# catropy.net
KiCad netlist of a schematic drawn in EAGLE
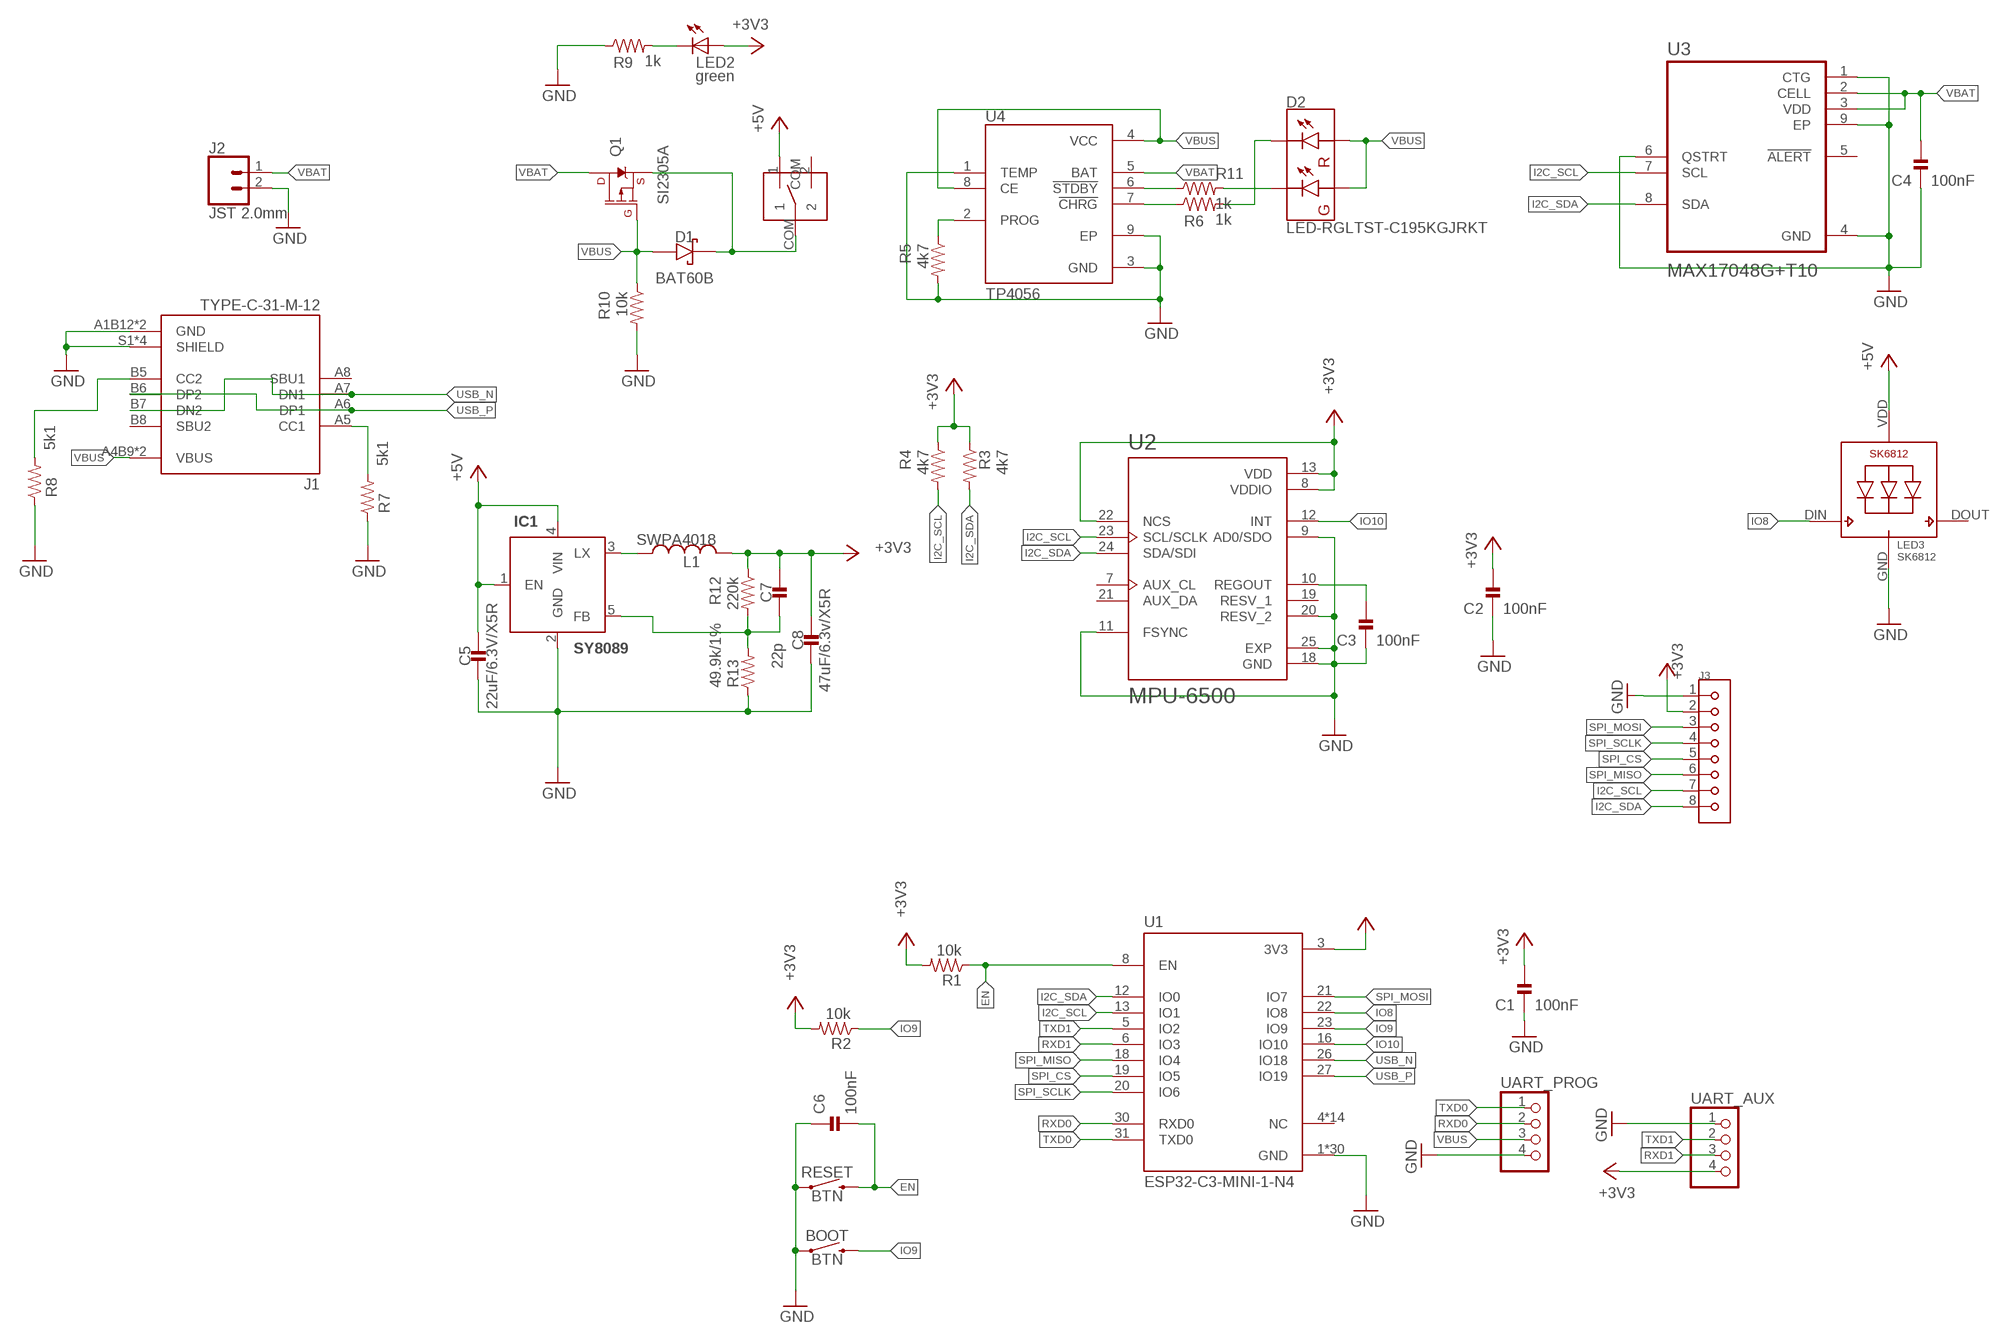
[diagram p0: schematic, sheet 1]

(export (version "E")
  (design (tool "Eeschema 10.0.6"))
  (components
    (comp (ref "BOOT")
      (value "BTN")
      (footprint "eagle-import:TACTILE_SWITCH_SMD_6.0X3.5MM")
      (fields (field (name "LCSC_PART") "C118141"))
      (libsource (lib "eagle-import") (part "MOMENTARY-SWITCH-SPST-SMD-6.0X3.5MM"))
    )
    (comp (ref "C1")
      (value "100nF")
      (footprint "eagle-import:0402_CAP")
      (libsource (lib "eagle-import") (part "CAPACITOR0402_CAP"))
    )
    (comp (ref "C2")
      (value "100nF")
      (footprint "eagle-import:0402_CAP")
      (libsource (lib "eagle-import") (part "CAPACITOR0402_CAP"))
    )
    (comp (ref "C3")
      (value "100nF")
      (footprint "eagle-import:0402_CAP")
      (libsource (lib "eagle-import") (part "CAPACITOR0402_CAP"))
    )
    (comp (ref "C4")
      (value "100nF")
      (footprint "eagle-import:0402_CAP")
      (libsource (lib "eagle-import") (part "CAPACITOR0402_CAP"))
    )
    (comp (ref "C5")
      (value "22uF/6.3V/X5R")
      (footprint "eagle-import:0603_CAP")
      (libsource (lib "eagle-import") (part "CAPACITOR0603_CAP"))
    )
    (comp (ref "C6")
      (value "100nF")
      (footprint "eagle-import:0402_CAP")
      (libsource (lib "eagle-import") (part "CAPACITOR0402_CAP"))
    )
    (comp (ref "C7")
      (value "22p")
      (footprint "eagle-import:0402_CAP")
      (libsource (lib "eagle-import") (part "CAPACITOR0402_CAP"))
    )
    (comp (ref "C8")
      (value "47uF/6.3v/X5R")
      (footprint "eagle-import:0805_CAP")
      (libsource (lib "eagle-import") (part "CAPACITOR0805_CAP"))
    )
    (comp (ref "D1")
      (value "BAT60B")
      (footprint "eagle-import:SOD323")
      (fields (field (name "LCSC_PART") "C22638"))
      (libsource (lib "eagle-import") (part "DIODE_SCHOTTKYSOD323"))
    )
    (comp (ref "D2")
      (value "LED-RGLTST-C195KGJRKT")
      (footprint "eagle-import:LTST-C195KGJRKT")
      (fields (field (name "LCSC_PART") "C125104"))
      (libsource (lib "eagle-import") (part "LED-RGLTST-C195KGJRKT"))
    )
    (comp (ref "IC1")
      (value "SY8089")
      (footprint "eagle-import:SOT23-5")
      (fields (field (name "LCSC_PART") "C78988"))
      (libsource (lib "eagle-import") (part "SY8089"))
    )
    (comp (ref "J1")
      (value "TYPE-C-31-M-12")
      (footprint "eagle-import:HRO_TYPE-C-31-M-12")
      (fields (field (name "MF") "HRO Electronics Co., Ltd.") (field (name "LCSC_PART") "C165948"))
      (libsource (lib "eagle-import") (part "TYPE-C-31-M-12"))
    )
    (comp (ref "J2")
      (value "JST 2.0mm")
      (footprint "eagle-import:JST-2-SMD")
      (fields (field (name "LCSC_PART") "C3029440"))
      (libsource (lib "eagle-import") (part "CONN_02-JST-2MM-SMT"))
    )
    (comp (ref "J3")
      (value "SM08B-SRSS-TB(LF)(SN)")
      (footprint "eagle-import:JST_SM08B-SRSS-TB(LF)(SN)")
      (fields (field (name "MF") "JST Sales") (field (name "LCSC_PART") "C160407"))
      (libsource (lib "eagle-import") (part "SM08B-SRSS-TB(LF)(SN)"))
    )
    (comp (ref "L1")
      (value "SWPA4018")
      (footprint "eagle-import:SWPA40XX")
      (fields (field (name "LCSC_PART") "C50543"))
      (libsource (lib "eagle-import") (part "SWPA40XX"))
    )
    (comp (ref "LED2")
      (value "green")
      (footprint "eagle-import:CHIPLED_0603")
      (fields (field (name "LCSC_PART") "C72043"))
      (libsource (lib "eagle-import") (part "LEDCHIPLED_0603"))
    )
    (comp (ref "LED3")
      (value "SK6812")
      (footprint "eagle-import:LED_EC3210R")
      (fields (field (name "LCSC_PART") "C2890041"))
      (libsource (lib "eagle-import") (part "SK6812_EC3210R"))
    )
    (comp (ref "Q1")
      (value "SI2305A")
      (footprint "eagle-import:SOT23-3")
      (fields (field (name "LCSC_PART") "C347488"))
      (libsource (lib "eagle-import") (part "MOSFET_PCH-SI2309DS"))
    )
    (comp (ref "R1")
      (value "10k")
      (footprint "eagle-import:0402_RES")
      (libsource (lib "eagle-import") (part "RESISTOR0402_RES"))
    )
    (comp (ref "R2")
      (value "10k")
      (footprint "eagle-import:0402_RES")
      (libsource (lib "eagle-import") (part "RESISTOR0402_RES"))
    )
    (comp (ref "R3")
      (value "4k7")
      (footprint "eagle-import:0402_RES")
      (libsource (lib "eagle-import") (part "RESISTOR0402_RES"))
    )
    (comp (ref "R4")
      (value "4k7")
      (footprint "eagle-import:0402_RES")
      (libsource (lib "eagle-import") (part "RESISTOR0402_RES"))
    )
    (comp (ref "R5")
      (value "4k7")
      (footprint "eagle-import:0402_RES")
      (libsource (lib "eagle-import") (part "RESISTOR0402_RES"))
    )
    (comp (ref "R6")
      (value "1k")
      (footprint "eagle-import:0402_RES")
      (libsource (lib "eagle-import") (part "RESISTOR0402_RES"))
    )
    (comp (ref "R7")
      (value "5k1")
      (footprint "eagle-import:0402_RES")
      (libsource (lib "eagle-import") (part "RESISTOR0402_RES"))
    )
    (comp (ref "R8")
      (value "5k1")
      (footprint "eagle-import:0402_RES")
      (libsource (lib "eagle-import") (part "RESISTOR0402_RES"))
    )
    (comp (ref "R9")
      (value "1k")
      (footprint "eagle-import:0402_RES")
      (libsource (lib "eagle-import") (part "RESISTOR0402_RES"))
    )
    (comp (ref "R10")
      (value "10k")
      (footprint "eagle-import:0402_RES")
      (libsource (lib "eagle-import") (part "RESISTOR0402_RES"))
    )
    (comp (ref "R11")
      (value "1k")
      (footprint "eagle-import:0402_RES")
      (libsource (lib "eagle-import") (part "RESISTOR0402_RES"))
    )
    (comp (ref "R12")
      (value "220k")
      (footprint "eagle-import:0402_RES")
      (libsource (lib "eagle-import") (part "RESISTOR0402_RES"))
    )
    (comp (ref "R13")
      (value "49.9k/1%")
      (footprint "eagle-import:0402_RES")
      (fields (field (name "LCSC_PART") "C208898"))
      (libsource (lib "eagle-import") (part "RESISTOR0402_RES"))
    )
    (comp (ref "RESET")
      (value "BTN")
      (footprint "eagle-import:TACTILE_SWITCH_SMD_6.0X3.5MM")
      (fields (field (name "LCSC_PART") "C118141"))
      (libsource (lib "eagle-import") (part "MOMENTARY-SWITCH-SPST-SMD-6.0X3.5MM"))
    )
    (comp (ref "U$1")
      (value "SK12D07VG4")
      (footprint "eagle-import:SK12D07VG4")
      (fields (field (name "MF") "C&K") (field (name "LCSC_PART") "C393937"))
      (libsource (lib "eagle-import") (part "SK12D07VG4"))
    )
    (comp (ref "U1")
      (value "ESP32-C3-MINI-1-N4")
      (footprint "eagle-import:XCVR_ESP32-C3-MINI-1-N4")
      (fields (field (name "MF") "Espressif Systems") (field (name "LCSC_PART") "C2838502"))
      (libsource (lib "eagle-import") (part "ESP32-C3-MINI-1-N4"))
    )
    (comp (ref "U2")
      (value "MPU-6500")
      (footprint "eagle-import:QFN40P300X300X95-25N")
      (fields (field (name "MF") "TDK InvenSense") (field (name "LCSC_PART") "C50278"))
      (libsource (lib "eagle-import") (part "MPU-6500"))
    )
    (comp (ref "U3")
      (value "MAX17048G+T10")
      (footprint "eagle-import:SON50P200X200X80-9N")
      (fields (field (name "MF") "Analog Devices") (field (name "LCSC_PART") "C2682616"))
      (libsource (lib "eagle-import") (part "MAX17048G+T10"))
    )
    (comp (ref "U4")
      (value "TP4056")
      (footprint "eagle-import:SOP127P600X175-9N")
      (fields (field (name "MF") "NanJing Top Power ASIC Corp."))
      (libsource (lib "eagle-import") (part "TP4056"))
    )
    (comp (ref "UART_AUX")
      (value "PINHD-1X4")
      (footprint "eagle-import:1X04")
      (libsource (lib "eagle-import") (part "PINHD-1X4"))
    )
    (comp (ref "UART_PROG")
      (value "PINHD-1X4")
      (footprint "eagle-import:1X04")
      (libsource (lib "eagle-import") (part "PINHD-1X4"))
    )
  )
  (nets
    (net (code "1") (name "+3V3") (class "Default")
      (node (ref "C1") (pin "2") (pinfunction "2_2") (pintype "bidirectional"))
      (node (ref "C2") (pin "2") (pinfunction "2_2") (pintype "bidirectional"))
      (node (ref "C7") (pin "1") (pinfunction "1_1") (pintype "bidirectional"))
      (node (ref "C8") (pin "P$1") (pinfunction "1_P$1") (pintype "bidirectional"))
      (node (ref "J3") (pin "2") (pinfunction "2_2") (pintype "passive"))
      (node (ref "L1") (pin "P$2") (pinfunction "2_P$2") (pintype "bidirectional"))
      (node (ref "LED2") (pin "A") (pinfunction "A_A") (pintype "passive"))
      (node (ref "R1") (pin "2") (pinfunction "2_2") (pintype "passive"))
      (node (ref "R12") (pin "1") (pinfunction "1_1") (pintype "passive"))
      (node (ref "R2") (pin "2") (pinfunction "2_2") (pintype "passive"))
      (node (ref "R3") (pin "1") (pinfunction "1_1") (pintype "passive"))
      (node (ref "R4") (pin "1") (pinfunction "1_1") (pintype "passive"))
      (node (ref "U1") (pin "3") (pinfunction "3V3_3") (pintype "power_in"))
      (node (ref "U2") (pin "13") (pinfunction "VDD_13") (pintype "power_in"))
      (node (ref "U2") (pin "22") (pinfunction "NCS_22") (pintype "input"))
      (node (ref "U2") (pin "8") (pinfunction "VDDIO_8") (pintype "power_in"))
      (node (ref "UART_AUX") (pin "4") (pinfunction "4_4") (pintype "passive"))
    )
    (net (code "2") (name "+5V") (class "Default")
      (node (ref "C5") (pin "1") (pinfunction "1_1") (pintype "bidirectional"))
      (node (ref "IC1") (pin "1") (pinfunction "EN_1") (pintype "input"))
      (node (ref "IC1") (pin "4") (pinfunction "VIN_4") (pintype "input"))
      (node (ref "LED3") (pin "VDD") (pinfunction "VDD_VDD") (pintype "power_in"))
      (node (ref "U$1") (pin "1") (pinfunction "1_1") (pintype "bidirectional"))
    )
    (net (code "3") (name "EN") (class "Default")
      (node (ref "C6") (pin "2") (pinfunction "2_2") (pintype "bidirectional"))
      (node (ref "R1") (pin "1") (pinfunction "1_1") (pintype "passive"))
      (node (ref "RESET") (pin "2") (pinfunction "2_2") (pintype "passive"))
      (node (ref "U1") (pin "8") (pinfunction "EN_8") (pintype "input"))
    )
    (net (code "4") (name "GND") (class "Default")
      (node (ref "BOOT") (pin "1") (pinfunction "1_1") (pintype "passive"))
      (node (ref "C1") (pin "1") (pinfunction "1_1") (pintype "bidirectional"))
      (node (ref "C2") (pin "1") (pinfunction "1_1") (pintype "bidirectional"))
      (node (ref "C3") (pin "1") (pinfunction "1_1") (pintype "bidirectional"))
      (node (ref "C4") (pin "1") (pinfunction "1_1") (pintype "bidirectional"))
      (node (ref "C5") (pin "2") (pinfunction "2_2") (pintype "bidirectional"))
      (node (ref "C6") (pin "1") (pinfunction "1_1") (pintype "bidirectional"))
      (node (ref "C8") (pin "P$2") (pinfunction "2_P$2") (pintype "bidirectional"))
      (node (ref "IC1") (pin "2") (pinfunction "GND_2") (pintype "power_in"))
      (node (ref "J1") (pin "A1B12") (pinfunction "GND_A1B12") (pintype "power_in"))
      (node (ref "J1") (pin "B1A12") (pinfunction "GND_B1A12") (pintype "power_in"))
      (node (ref "J1") (pin "S1") (pinfunction "SHIELD_S1") (pintype "passive"))
      (node (ref "J1") (pin "S2") (pinfunction "SHIELD_S2") (pintype "passive"))
      (node (ref "J1") (pin "S3") (pinfunction "SHIELD_S3") (pintype "passive"))
      (node (ref "J1") (pin "S4") (pinfunction "SHIELD_S4") (pintype "passive"))
      (node (ref "J2") (pin "2") (pinfunction "1_2") (pintype "passive"))
      (node (ref "J3") (pin "1") (pinfunction "1_1") (pintype "passive"))
      (node (ref "LED3") (pin "GND") (pinfunction "GND_GND") (pintype "power_in"))
      (node (ref "R10") (pin "2") (pinfunction "2_2") (pintype "passive"))
      (node (ref "R13") (pin "1") (pinfunction "1_1") (pintype "passive"))
      (node (ref "R5") (pin "2") (pinfunction "2_2") (pintype "passive"))
      (node (ref "R7") (pin "1") (pinfunction "1_1") (pintype "passive"))
      (node (ref "R8") (pin "1") (pinfunction "1_1") (pintype "passive"))
      (node (ref "R9") (pin "1") (pinfunction "1_1") (pintype "passive"))
      (node (ref "RESET") (pin "1") (pinfunction "1_1") (pintype "passive"))
      (node (ref "U1") (pin "1") (pinfunction "GND_1") (pintype "power_in"))
      (node (ref "U1") (pin "11") (pinfunction "GND_11") (pintype "power_in"))
      (node (ref "U1") (pin "14") (pinfunction "GND_14") (pintype "power_in"))
      (node (ref "U1") (pin "2") (pinfunction "GND_2") (pintype "power_in"))
      (node (ref "U1") (pin "36") (pinfunction "GND_36") (pintype "power_in"))
      (node (ref "U1") (pin "37") (pinfunction "GND_37") (pintype "power_in"))
      (node (ref "U1") (pin "38") (pinfunction "GND_38") (pintype "power_in"))
      (node (ref "U1") (pin "39") (pinfunction "GND_39") (pintype "power_in"))
      (node (ref "U1") (pin "40") (pinfunction "GND_40") (pintype "power_in"))
      (node (ref "U1") (pin "41") (pinfunction "GND_41") (pintype "power_in"))
      (node (ref "U1") (pin "42") (pinfunction "GND_42") (pintype "power_in"))
      (node (ref "U1") (pin "43") (pinfunction "GND_43") (pintype "power_in"))
      (node (ref "U1") (pin "44") (pinfunction "GND_44") (pintype "power_in"))
      (node (ref "U1") (pin "45") (pinfunction "GND_45") (pintype "power_in"))
      (node (ref "U1") (pin "46") (pinfunction "GND_46") (pintype "power_in"))
      (node (ref "U1") (pin "47") (pinfunction "GND_47") (pintype "power_in"))
      (node (ref "U1") (pin "48") (pinfunction "GND_48") (pintype "power_in"))
      (node (ref "U1") (pin "49_1") (pinfunction "GND_49_1") (pintype "power_in"))
      (node (ref "U1") (pin "49_2") (pinfunction "GND_49_2") (pintype "power_in"))
      (node (ref "U1") (pin "49_3") (pinfunction "GND_49_3") (pintype "power_in"))
      (node (ref "U1") (pin "49_4") (pinfunction "GND_49_4") (pintype "power_in"))
      (node (ref "U1") (pin "49_5") (pinfunction "GND_49_5") (pintype "power_in"))
      (node (ref "U1") (pin "49_6") (pinfunction "GND_49_6") (pintype "power_in"))
      (node (ref "U1") (pin "49_7") (pinfunction "GND_49_7") (pintype "power_in"))
      (node (ref "U1") (pin "49_8") (pinfunction "GND_49_8") (pintype "power_in"))
      (node (ref "U1") (pin "49_9") (pinfunction "GND_49_9") (pintype "power_in"))
      (node (ref "U1") (pin "50") (pinfunction "GND_50") (pintype "power_in"))
      (node (ref "U1") (pin "51") (pinfunction "GND_51") (pintype "power_in"))
      (node (ref "U1") (pin "52") (pinfunction "GND_52") (pintype "power_in"))
      (node (ref "U1") (pin "53") (pinfunction "GND_53") (pintype "power_in"))
      (node (ref "U2") (pin "11") (pinfunction "FSYNC_11") (pintype "input"))
      (node (ref "U2") (pin "18") (pinfunction "GND_18") (pintype "power_in"))
      (node (ref "U2") (pin "20") (pinfunction "RESV_2_20") (pintype "passive"))
      (node (ref "U2") (pin "25") (pinfunction "EXP_25") (pintype "passive"))
      (node (ref "U2") (pin "9") (pinfunction "AD0/SDO_9") (pintype "output"))
      (node (ref "U3") (pin "1") (pinfunction "CTG_1") (pintype "power_in"))
      (node (ref "U3") (pin "4") (pinfunction "GND_4") (pintype "power_in"))
      (node (ref "U3") (pin "6") (pinfunction "QSTRT_6") (pintype "input"))
      (node (ref "U3") (pin "9") (pinfunction "EP_9") (pintype "power_in"))
      (node (ref "U4") (pin "1") (pinfunction "TEMP_1") (pintype "input"))
      (node (ref "U4") (pin "3") (pinfunction "GND_3") (pintype "power_in"))
      (node (ref "U4") (pin "9") (pinfunction "EP_9") (pintype "passive"))
      (node (ref "UART_AUX") (pin "1") (pinfunction "1_1") (pintype "passive"))
      (node (ref "UART_PROG") (pin "4") (pinfunction "4_4") (pintype "passive"))
    )
    (net (code "5") (name "I2C_SCL") (class "Default")
      (node (ref "J3") (pin "7") (pinfunction "7_7") (pintype "passive"))
      (node (ref "R4") (pin "2") (pinfunction "2_2") (pintype "passive"))
      (node (ref "U1") (pin "13") (pinfunction "IO1_13") (pintype "bidirectional"))
      (node (ref "U2") (pin "23") (pinfunction "SCL/SCLK_23") (pintype "input"))
      (node (ref "U3") (pin "7") (pinfunction "SCL_7") (pintype "input"))
    )
    (net (code "6") (name "I2C_SDA") (class "Default")
      (node (ref "J3") (pin "8") (pinfunction "8_8") (pintype "passive"))
      (node (ref "R3") (pin "2") (pinfunction "2_2") (pintype "passive"))
      (node (ref "U1") (pin "12") (pinfunction "IO0_12") (pintype "bidirectional"))
      (node (ref "U2") (pin "24") (pinfunction "SDA/SDI_24") (pintype "bidirectional"))
      (node (ref "U3") (pin "8") (pinfunction "SDA_8") (pintype "bidirectional"))
    )
    (net (code "7") (name "IO8") (class "Default")
      (node (ref "LED3") (pin "DIN") (pinfunction "DI_DIN") (pintype "input"))
      (node (ref "U1") (pin "22") (pinfunction "IO8_22") (pintype "bidirectional"))
    )
    (net (code "8") (name "IO9") (class "Default")
      (node (ref "BOOT") (pin "2") (pinfunction "2_2") (pintype "passive"))
      (node (ref "R2") (pin "1") (pinfunction "1_1") (pintype "passive"))
      (node (ref "U1") (pin "23") (pinfunction "IO9_23") (pintype "bidirectional"))
    )
    (net (code "9") (name "IO10") (class "Default")
      (node (ref "U1") (pin "16") (pinfunction "IO10_16") (pintype "bidirectional"))
      (node (ref "U2") (pin "12") (pinfunction "INT_12") (pintype "output"))
    )
    (net (code "10") (name "Net-(D1-CATHODE)") (class "Default")
      (node (ref "D1") (pin "P$1") (pinfunction "CATHODE_P$1") (pintype "bidirectional"))
      (node (ref "Q1") (pin "2") (pinfunction "S_2") (pintype "bidirectional"))
      (node (ref "U$1") (pin "COM") (pinfunction "COM_COM") (pintype "bidirectional"))
    )
    (net (code "11") (name "Net-(D2-GC)") (class "Default")
      (node (ref "D2") (pin "P$3") (pinfunction "GC_P$3") (pintype "passive"))
      (node (ref "R11") (pin "2") (pinfunction "2_2") (pintype "passive"))
    )
    (net (code "12") (name "Net-(D2-RC)") (class "Default")
      (node (ref "D2") (pin "P$4") (pinfunction "RC_P$4") (pintype "passive"))
      (node (ref "R6") (pin "2") (pinfunction "2_2") (pintype "passive"))
    )
    (net (code "13") (name "Net-(IC1-FB)") (class "Default")
      (node (ref "C7") (pin "2") (pinfunction "2_2") (pintype "bidirectional"))
      (node (ref "IC1") (pin "5") (pinfunction "FB_5") (pintype "input"))
      (node (ref "R12") (pin "2") (pinfunction "2_2") (pintype "passive"))
      (node (ref "R13") (pin "2") (pinfunction "2_2") (pintype "passive"))
    )
    (net (code "14") (name "Net-(IC1-LX)") (class "Default")
      (node (ref "IC1") (pin "3") (pinfunction "LX_3") (pintype "output"))
      (node (ref "L1") (pin "P$1") (pinfunction "1_P$1") (pintype "bidirectional"))
    )
    (net (code "15") (name "Net-(J1-CC1)") (class "Default")
      (node (ref "J1") (pin "A5") (pinfunction "CC1_A5") (pintype "bidirectional"))
      (node (ref "R7") (pin "2") (pinfunction "2_2") (pintype "passive"))
    )
    (net (code "16") (name "Net-(J1-CC2)") (class "Default")
      (node (ref "J1") (pin "B5") (pinfunction "CC2_B5") (pintype "bidirectional"))
      (node (ref "R8") (pin "2") (pinfunction "2_2") (pintype "passive"))
    )
    (net (code "17") (name "Net-(LED2-PadC)") (class "Default")
      (node (ref "LED2") (pin "C") (pinfunction "C_C") (pintype "passive"))
      (node (ref "R9") (pin "2") (pinfunction "2_2") (pintype "passive"))
    )
    (net (code "18") (name "Net-(U2-REGOUT)") (class "Default")
      (node (ref "C3") (pin "2") (pinfunction "2_2") (pintype "bidirectional"))
      (node (ref "U2") (pin "10") (pinfunction "REGOUT_10") (pintype "output"))
    )
    (net (code "19") (name "Net-(U4-PROG)") (class "Default")
      (node (ref "R5") (pin "1") (pinfunction "1_1") (pintype "passive"))
      (node (ref "U4") (pin "2") (pinfunction "PROG_2") (pintype "bidirectional"))
    )
    (net (code "20") (name "Net-(U4-~{CHRG})") (class "Default")
      (node (ref "R6") (pin "1") (pinfunction "1_1") (pintype "passive"))
      (node (ref "U4") (pin "7") (pinfunction "~{CHRG}_7") (pintype "output"))
    )
    (net (code "21") (name "Net-(U4-~{STDBY})") (class "Default")
      (node (ref "R11") (pin "1") (pinfunction "1_1") (pintype "passive"))
      (node (ref "U4") (pin "6") (pinfunction "~{STDBY}_6") (pintype "output"))
    )
    (net (code "22") (name "RXD0") (class "Default")
      (node (ref "U1") (pin "30") (pinfunction "RXD0_30") (pintype "bidirectional"))
      (node (ref "UART_PROG") (pin "2") (pinfunction "2_2") (pintype "passive"))
    )
    (net (code "23") (name "RXD1") (class "Default")
      (node (ref "U1") (pin "6") (pinfunction "IO3_6") (pintype "bidirectional"))
      (node (ref "UART_AUX") (pin "3") (pinfunction "3_3") (pintype "passive"))
    )
    (net (code "24") (name "SPI_CS") (class "Default")
      (node (ref "J3") (pin "5") (pinfunction "5_5") (pintype "passive"))
      (node (ref "U1") (pin "19") (pinfunction "IO5_19") (pintype "bidirectional"))
    )
    (net (code "25") (name "SPI_MISO") (class "Default")
      (node (ref "J3") (pin "6") (pinfunction "6_6") (pintype "passive"))
      (node (ref "U1") (pin "18") (pinfunction "IO4_18") (pintype "bidirectional"))
    )
    (net (code "26") (name "SPI_MOSI") (class "Default")
      (node (ref "J3") (pin "3") (pinfunction "3_3") (pintype "passive"))
      (node (ref "U1") (pin "21") (pinfunction "IO7_21") (pintype "bidirectional"))
    )
    (net (code "27") (name "SPI_SCLK") (class "Default")
      (node (ref "J3") (pin "4") (pinfunction "4_4") (pintype "passive"))
      (node (ref "U1") (pin "20") (pinfunction "IO6_20") (pintype "bidirectional"))
    )
    (net (code "28") (name "TXD0") (class "Default")
      (node (ref "U1") (pin "31") (pinfunction "TXD0_31") (pintype "bidirectional"))
      (node (ref "UART_PROG") (pin "1") (pinfunction "1_1") (pintype "passive"))
    )
    (net (code "29") (name "TXD1") (class "Default")
      (node (ref "U1") (pin "5") (pinfunction "IO2_5") (pintype "bidirectional"))
      (node (ref "UART_AUX") (pin "2") (pinfunction "2_2") (pintype "passive"))
    )
    (net (code "30") (name "USB_N") (class "Default")
      (node (ref "J1") (pin "A7") (pinfunction "DN1_A7") (pintype "bidirectional"))
      (node (ref "J1") (pin "B7") (pinfunction "DN2_B7") (pintype "bidirectional"))
      (node (ref "U1") (pin "26") (pinfunction "IO18_26") (pintype "bidirectional"))
    )
    (net (code "31") (name "USB_P") (class "Default")
      (node (ref "J1") (pin "A6") (pinfunction "DP1_A6") (pintype "bidirectional"))
      (node (ref "J1") (pin "B6") (pinfunction "DP2_B6") (pintype "bidirectional"))
      (node (ref "U1") (pin "27") (pinfunction "IO19_27") (pintype "bidirectional"))
    )
    (net (code "32") (name "VBAT") (class "Default")
      (node (ref "C4") (pin "2") (pinfunction "2_2") (pintype "bidirectional"))
      (node (ref "J2") (pin "1") (pinfunction "2_1") (pintype "passive"))
      (node (ref "Q1") (pin "3") (pinfunction "D_3") (pintype "bidirectional"))
      (node (ref "U3") (pin "2") (pinfunction "CELL_2") (pintype "power_in"))
      (node (ref "U3") (pin "3") (pinfunction "VDD_3") (pintype "power_in"))
      (node (ref "U4") (pin "5") (pinfunction "BAT_5") (pintype "output"))
    )
    (net (code "33") (name "VBUS") (class "Default")
      (node (ref "D1") (pin "P$2") (pinfunction "ANODE_P$2") (pintype "bidirectional"))
      (node (ref "D2") (pin "P$1") (pinfunction "GA_P$1") (pintype "passive"))
      (node (ref "D2") (pin "P$2") (pinfunction "RA_P$2") (pintype "passive"))
      (node (ref "J1") (pin "A4B9") (pinfunction "VBUS_A4B9") (pintype "power_in"))
      (node (ref "J1") (pin "B4A9") (pinfunction "VBUS_B4A9") (pintype "power_in"))
      (node (ref "Q1") (pin "1") (pinfunction "G_1") (pintype "bidirectional"))
      (node (ref "R10") (pin "1") (pinfunction "1_1") (pintype "passive"))
      (node (ref "U4") (pin "4") (pinfunction "VCC_4") (pintype "power_in"))
      (node (ref "U4") (pin "8") (pinfunction "CE_8") (pintype "input"))
      (node (ref "UART_PROG") (pin "3") (pinfunction "3_3") (pintype "passive"))
    )
    (net (code "34") (name "unconnected-(J1-SBU1-PadA8)") (class "Default")
      (node (ref "J1") (pin "A8") (pinfunction "SBU1_A8") (pintype "bidirectional"))
    )
    (net (code "35") (name "unconnected-(J1-SBU2-PadB8)") (class "Default")
      (node (ref "J1") (pin "B8") (pinfunction "SBU2_B8") (pintype "bidirectional"))
    )
    (net (code "36") (name "unconnected-(LED3-DO-PadDOUT)") (class "Default")
      (node (ref "LED3") (pin "DOUT") (pinfunction "DO_DOUT") (pintype "output"))
    )
    (net (code "37") (name "unconnected-(U$1-Pad2)") (class "Default")
      (node (ref "U$1") (pin "2") (pinfunction "2_2") (pintype "bidirectional"))
    )
    (net (code "38") (name "unconnected-(U1-NC-Pad4)") (class "Default")
      (node (ref "U1") (pin "4") (pinfunction "NC_4") (pintype "no_connect"))
    )
    (net (code "39") (name "unconnected-(U1-NC-Pad7)") (class "Default")
      (node (ref "U1") (pin "7") (pinfunction "NC_7") (pintype "no_connect"))
    )
    (net (code "40") (name "unconnected-(U1-NC-Pad9)") (class "Default")
      (node (ref "U1") (pin "9") (pinfunction "NC_9") (pintype "no_connect"))
    )
    (net (code "41") (name "unconnected-(U1-NC-Pad10)") (class "Default")
      (node (ref "U1") (pin "10") (pinfunction "NC_10") (pintype "no_connect"))
    )
    (net (code "42") (name "unconnected-(U1-NC-Pad15)") (class "Default")
      (node (ref "U1") (pin "15") (pinfunction "NC_15") (pintype "no_connect"))
    )
    (net (code "43") (name "unconnected-(U1-NC-Pad17)") (class "Default")
      (node (ref "U1") (pin "17") (pinfunction "NC_17") (pintype "no_connect"))
    )
    (net (code "44") (name "unconnected-(U1-NC-Pad24)") (class "Default")
      (node (ref "U1") (pin "24") (pinfunction "NC_24") (pintype "no_connect"))
    )
    (net (code "45") (name "unconnected-(U1-NC-Pad25)") (class "Default")
      (node (ref "U1") (pin "25") (pinfunction "NC_25") (pintype "no_connect"))
    )
    (net (code "46") (name "unconnected-(U1-NC-Pad28)") (class "Default")
      (node (ref "U1") (pin "28") (pinfunction "NC_28") (pintype "no_connect"))
    )
    (net (code "47") (name "unconnected-(U1-NC-Pad29)") (class "Default")
      (node (ref "U1") (pin "29") (pinfunction "NC_29") (pintype "no_connect"))
    )
    (net (code "48") (name "unconnected-(U1-NC-Pad32)") (class "Default")
      (node (ref "U1") (pin "32") (pinfunction "NC_32") (pintype "no_connect"))
    )
    (net (code "49") (name "unconnected-(U1-NC-Pad33)") (class "Default")
      (node (ref "U1") (pin "33") (pinfunction "NC_33") (pintype "no_connect"))
    )
    (net (code "50") (name "unconnected-(U1-NC-Pad34)") (class "Default")
      (node (ref "U1") (pin "34") (pinfunction "NC_34") (pintype "no_connect"))
    )
    (net (code "51") (name "unconnected-(U1-NC-Pad35)") (class "Default")
      (node (ref "U1") (pin "35") (pinfunction "NC_35") (pintype "no_connect"))
    )
    (net (code "52") (name "unconnected-(U2-AUX_CL-Pad7)") (class "Default")
      (node (ref "U2") (pin "7") (pinfunction "AUX_CL_7") (pintype "input"))
    )
    (net (code "53") (name "unconnected-(U2-AUX_DA-Pad21)") (class "Default")
      (node (ref "U2") (pin "21") (pinfunction "AUX_DA_21") (pintype "bidirectional"))
    )
    (net (code "54") (name "unconnected-(U2-RESV_1-Pad19)") (class "Default")
      (node (ref "U2") (pin "19") (pinfunction "RESV_1_19") (pintype "passive"))
    )
    (net (code "55") (name "unconnected-(U3-~{ALERT}-Pad5)") (class "Default")
      (node (ref "U3") (pin "5") (pinfunction "~{ALERT}_5") (pintype "output"))
    )
  )
)
